# sheet_top.net
KiCad netlist of a schematic drawn in Altium Designer
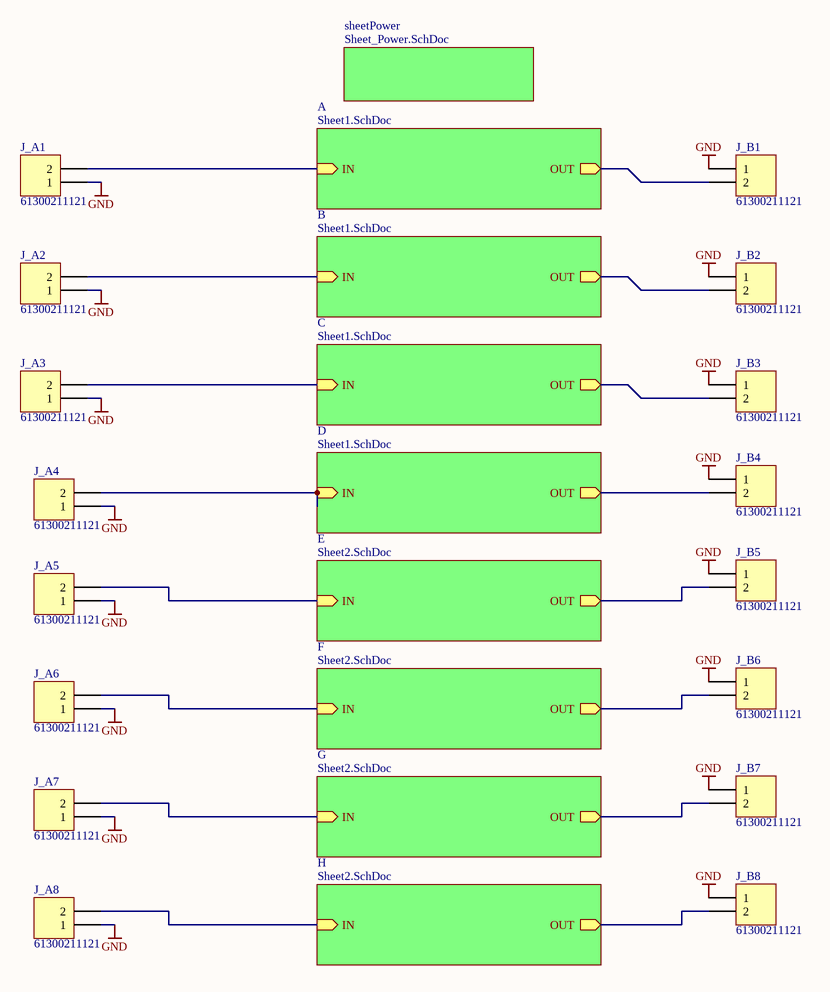
[diagram p0: sheet_top.SchDoc]

(export (version "E")
  (design (tool "Eeschema 10.0.6"))
  (components
    (comp (ref "J_A1")
      (value "61300211121")
      (footprint "61300211121")
      (description "2Pol; gerade; WR-PHD 2.54 mm THT Pin Header")
      (fields (field (name "MANUFACTURER") "Wurth Electronics"))
      (libsource (lib "") (part "CMP-001-0071-1_1"))
    )
    (comp (ref "J_A2")
      (value "61300211121")
      (footprint "61300211121")
      (description "2Pol; gerade; WR-PHD 2.54 mm THT Pin Header")
      (fields (field (name "MANUFACTURER") "Wurth Electronics"))
      (libsource (lib "") (part "CMP-001-0071-1_1"))
    )
    (comp (ref "J_A3")
      (value "61300211121")
      (footprint "61300211121")
      (description "2Pol; gerade; WR-PHD 2.54 mm THT Pin Header")
      (fields (field (name "MANUFACTURER") "Wurth Electronics"))
      (libsource (lib "") (part "CMP-001-0071-1_1"))
    )
    (comp (ref "J_A4")
      (value "61300211121")
      (footprint "61300211121")
      (description "2Pol; gerade; WR-PHD 2.54 mm THT Pin Header")
      (fields (field (name "MANUFACTURER") "Wurth Electronics"))
      (libsource (lib "") (part "CMP-001-0071-1_1"))
    )
    (comp (ref "J_A5")
      (value "61300211121")
      (footprint "61300211121")
      (description "2Pol; gerade; WR-PHD 2.54 mm THT Pin Header")
      (fields (field (name "MANUFACTURER") "Wurth Electronics"))
      (libsource (lib "") (part "CMP-001-0071-1_1"))
    )
    (comp (ref "J_A6")
      (value "61300211121")
      (footprint "61300211121")
      (description "2Pol; gerade; WR-PHD 2.54 mm THT Pin Header")
      (fields (field (name "MANUFACTURER") "Wurth Electronics"))
      (libsource (lib "") (part "CMP-001-0071-1_1"))
    )
    (comp (ref "J_A7")
      (value "61300211121")
      (footprint "61300211121")
      (description "2Pol; gerade; WR-PHD 2.54 mm THT Pin Header")
      (fields (field (name "MANUFACTURER") "Wurth Electronics"))
      (libsource (lib "") (part "CMP-001-0071-1_1"))
    )
    (comp (ref "J_A8")
      (value "61300211121")
      (footprint "61300211121")
      (description "2Pol; gerade; WR-PHD 2.54 mm THT Pin Header")
      (fields (field (name "MANUFACTURER") "Wurth Electronics"))
      (libsource (lib "") (part "CMP-001-0071-1_1"))
    )
    (comp (ref "J_B1")
      (value "61300211121")
      (footprint "61300211121")
      (description "2Pol; gerade; WR-PHD 2.54 mm THT Pin Header")
      (fields (field (name "MANUFACTURER") "Wurth Electronics"))
      (libsource (lib "Altium Vault EMBL 3") (part "61300211121"))
    )
    (comp (ref "J_B2")
      (value "61300211121")
      (footprint "61300211121")
      (description "2Pol; gerade; WR-PHD 2.54 mm THT Pin Header")
      (fields (field (name "MANUFACTURER") "Wurth Electronics"))
      (libsource (lib "Altium Vault EMBL 3") (part "CMP-001-0071-1"))
    )
    (comp (ref "J_B3")
      (value "61300211121")
      (footprint "61300211121")
      (description "2Pol; gerade; WR-PHD 2.54 mm THT Pin Header")
      (fields (field (name "MANUFACTURER") "Wurth Electronics"))
      (libsource (lib "Altium Vault EMBL 3") (part "CMP-001-0071-1"))
    )
    (comp (ref "J_B4")
      (value "61300211121")
      (footprint "61300211121")
      (description "2Pol; gerade; WR-PHD 2.54 mm THT Pin Header")
      (fields (field (name "MANUFACTURER") "Wurth Electronics"))
      (libsource (lib "Altium Vault EMBL 3") (part "CMP-001-0071-1"))
    )
    (comp (ref "J_B5")
      (value "61300211121")
      (footprint "61300211121")
      (description "2Pol; gerade; WR-PHD 2.54 mm THT Pin Header")
      (fields (field (name "MANUFACTURER") "Wurth Electronics"))
      (libsource (lib "Altium Vault EMBL 3") (part "CMP-001-0071-1"))
    )
    (comp (ref "J_B6")
      (value "61300211121")
      (footprint "61300211121")
      (description "2Pol; gerade; WR-PHD 2.54 mm THT Pin Header")
      (fields (field (name "MANUFACTURER") "Wurth Electronics"))
      (libsource (lib "Altium Vault EMBL 3") (part "CMP-001-0071-1"))
    )
    (comp (ref "J_B7")
      (value "61300211121")
      (footprint "61300211121")
      (description "2Pol; gerade; WR-PHD 2.54 mm THT Pin Header")
      (fields (field (name "MANUFACTURER") "Wurth Electronics"))
      (libsource (lib "Altium Vault EMBL 3") (part "CMP-001-0071-1"))
    )
    (comp (ref "J_B8")
      (value "61300211121")
      (footprint "61300211121")
      (description "2Pol; gerade; WR-PHD 2.54 mm THT Pin Header")
      (fields (field (name "MANUFACTURER") "Wurth Electronics"))
      (libsource (lib "Altium Vault EMBL 3") (part "CMP-001-0071-1"))
    )
  )
  (nets
    (net (code "1") (name "/IN") (class "Default")
      (node (ref "J_A8") (pin "2") (pinfunction "2_2") (pintype "passive"))
    )
    (net (code "2") (name "/IN_1") (class "Default")
      (node (ref "J_A1") (pin "2") (pinfunction "2_2") (pintype "passive"))
    )
    (net (code "3") (name "/IN_2") (class "Default")
      (node (ref "J_A2") (pin "2") (pinfunction "2_2") (pintype "passive"))
    )
    (net (code "4") (name "/IN_3") (class "Default")
      (node (ref "J_A3") (pin "2") (pinfunction "2_2") (pintype "passive"))
    )
    (net (code "5") (name "/IN_4") (class "Default")
      (node (ref "J_A4") (pin "2") (pinfunction "2_2") (pintype "passive"))
    )
    (net (code "6") (name "/IN_5") (class "Default")
      (node (ref "J_A5") (pin "2") (pinfunction "2_2") (pintype "passive"))
    )
    (net (code "7") (name "/IN_6") (class "Default")
      (node (ref "J_A6") (pin "2") (pinfunction "2_2") (pintype "passive"))
    )
    (net (code "8") (name "/IN_7") (class "Default")
      (node (ref "J_A7") (pin "2") (pinfunction "2_2") (pintype "passive"))
    )
    (net (code "9") (name "/OUT") (class "Default")
      (node (ref "J_B2") (pin "2") (pinfunction "2_2") (pintype "passive"))
    )
    (net (code "10") (name "/OUT_1") (class "Default")
      (node (ref "J_B3") (pin "2") (pinfunction "2_2") (pintype "passive"))
    )
    (net (code "11") (name "/OUT_2") (class "Default")
      (node (ref "J_B4") (pin "2") (pinfunction "2_2") (pintype "passive"))
    )
    (net (code "12") (name "/OUT_3") (class "Default")
      (node (ref "J_B5") (pin "2") (pinfunction "2_2") (pintype "passive"))
    )
    (net (code "13") (name "/OUT_4") (class "Default")
      (node (ref "J_B7") (pin "2") (pinfunction "2_2") (pintype "passive"))
    )
    (net (code "14") (name "/OUT_5") (class "Default")
      (node (ref "J_B8") (pin "2") (pinfunction "2_2") (pintype "passive"))
    )
    (net (code "15") (name "/OUT_6") (class "Default")
      (node (ref "J_B6") (pin "2") (pinfunction "2_2") (pintype "passive"))
    )
    (net (code "16") (name "/OUT_7") (class "Default")
      (node (ref "J_B1") (pin "2") (pinfunction "2_2") (pintype "passive"))
    )
    (net (code "17") (name "GND") (class "Default")
      (node (ref "J_A1") (pin "1") (pinfunction "1_1") (pintype "passive"))
      (node (ref "J_A2") (pin "1") (pinfunction "1_1") (pintype "passive"))
      (node (ref "J_A3") (pin "1") (pinfunction "1_1") (pintype "passive"))
      (node (ref "J_A4") (pin "1") (pinfunction "1_1") (pintype "passive"))
      (node (ref "J_A5") (pin "1") (pinfunction "1_1") (pintype "passive"))
      (node (ref "J_A6") (pin "1") (pinfunction "1_1") (pintype "passive"))
      (node (ref "J_A7") (pin "1") (pinfunction "1_1") (pintype "passive"))
      (node (ref "J_A8") (pin "1") (pinfunction "1_1") (pintype "passive"))
      (node (ref "J_B1") (pin "1") (pinfunction "1_1") (pintype "passive"))
      (node (ref "J_B2") (pin "1") (pinfunction "1_1") (pintype "passive"))
      (node (ref "J_B3") (pin "1") (pinfunction "1_1") (pintype "passive"))
      (node (ref "J_B4") (pin "1") (pinfunction "1_1") (pintype "passive"))
      (node (ref "J_B5") (pin "1") (pinfunction "1_1") (pintype "passive"))
      (node (ref "J_B6") (pin "1") (pinfunction "1_1") (pintype "passive"))
      (node (ref "J_B7") (pin "1") (pinfunction "1_1") (pintype "passive"))
      (node (ref "J_B8") (pin "1") (pinfunction "1_1") (pintype "passive"))
    )
  )
)
